# clock_generator.net
KiCad netlist of a schematic drawn in Altium Designer
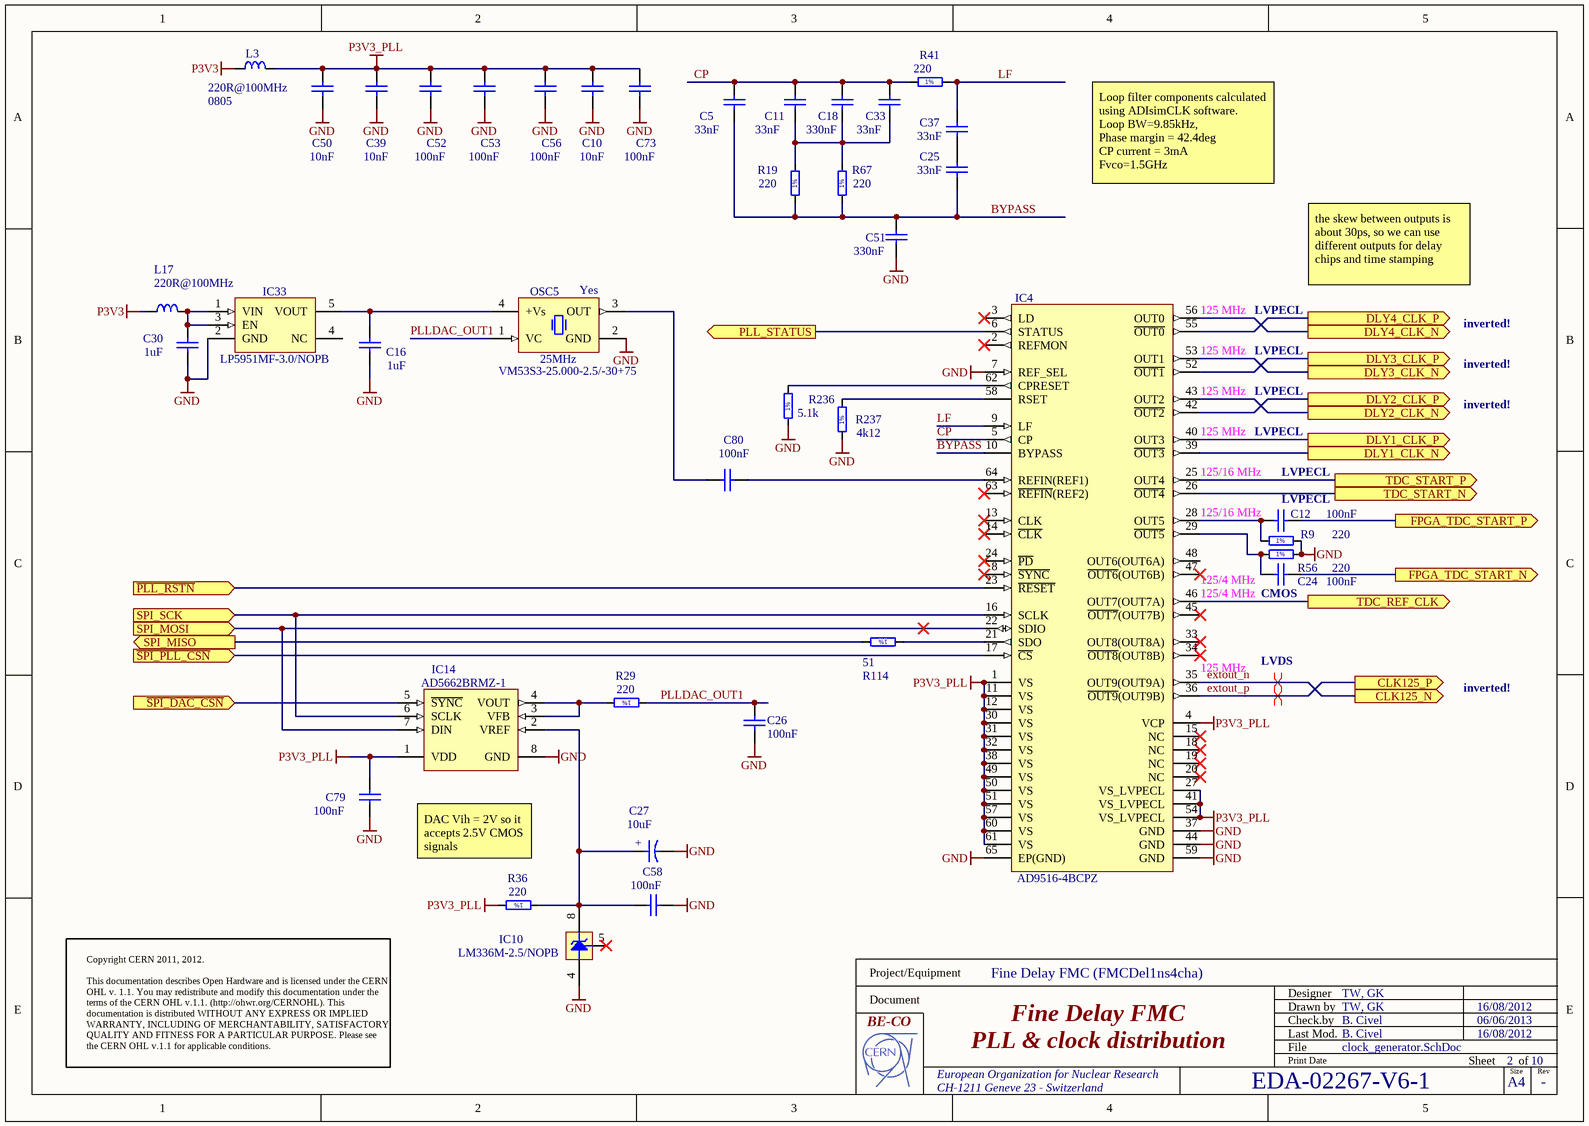
[diagram p0: clock_generator.SchDoc]

(export (version "E")
  (design (tool "Eeschema 10.0.6"))
  (components
    (comp (ref "C5")
      (value "33nF")
      (footprint "CAPC1608X87N")
      (description "Non-polarised capacitor")
      (fields
        (field (name "PART NUMBER") "CC0603_33NF_25V_10%_X7R")
        (field (name "VOLTAGE") "25V")
        (field (name "AUTHOR") "CERN DEM JLC")
      )
      (libsource (lib "Capacitors") (part "Capacitor - non polarized"))
    )
    (comp (ref "C10")
      (value "10nF")
      (footprint "CAPC1608X87N")
      (description "Non-polarised capacitor")
      (fields
        (field (name "PART NUMBER") "CC0603_10NF_50V_10%_X7R")
        (field (name "VOLTAGE") "50V")
        (field (name "AUTHOR") "CERN DEM JLC")
      )
      (libsource (lib "Capacitors") (part "Capacitor - non polarized"))
    )
    (comp (ref "C11")
      (value "33nF")
      (footprint "CAPC1608X87N")
      (description "Non-polarised capacitor")
      (fields
        (field (name "PART NUMBER") "CC0603_33NF_25V_10%_X7R")
        (field (name "VOLTAGE") "25V")
        (field (name "AUTHOR") "CERN DEM JLC")
      )
      (libsource (lib "Capacitors") (part "Capacitor - non polarized"))
    )
    (comp (ref "C12")
      (value "100nF")
      (footprint "CAPC1608X87N")
      (description "Non-polarised capacitor")
      (fields
        (field (name "PART NUMBER") "CC0603_100NF_50V_10%_X7R")
        (field (name "VOLTAGE") "50V")
        (field (name "AUTHOR") "CERN DEM JLC")
      )
      (libsource (lib "Capacitors") (part "Capacitor - non polarized"))
    )
    (comp (ref "C16")
      (value "1uF")
      (footprint "CAPC2012X140N")
      (description "Non-polarised capacitor")
      (fields
        (field (name "PART NUMBER") "CC0805_1UF_35V_20%_X7R")
        (field (name "VOLTAGE") "35V")
        (field (name "AUTHOR") "CERN DEM JLC")
      )
      (libsource (lib "Capacitors") (part "Capacitor - non polarized"))
    )
    (comp (ref "C18")
      (value "330nF")
      (footprint "CAPC1608X87N")
      (description "Non-polarised capacitor")
      (fields
        (field (name "PART NUMBER") "CC0603_330NF_16V_10%_X5R")
        (field (name "VOLTAGE") "16V")
        (field (name "AUTHOR") "CERN DEM JLC")
      )
      (libsource (lib "Capacitors") (part "Capacitor - non polarized"))
    )
    (comp (ref "C24")
      (value "100nF")
      (footprint "CAPC1608X87N")
      (description "Non-polarised capacitor")
      (fields
        (field (name "PART NUMBER") "CC0603_100NF_50V_10%_X7R")
        (field (name "VOLTAGE") "50V")
        (field (name "AUTHOR") "CERN DEM JLC")
      )
      (libsource (lib "Capacitors") (part "Capacitor - non polarized"))
    )
    (comp (ref "C25")
      (value "33nF")
      (footprint "CAPC1608X87N")
      (description "Non-polarised capacitor")
      (fields
        (field (name "PART NUMBER") "CC0603_33NF_25V_10%_X7R")
        (field (name "VOLTAGE") "25V")
        (field (name "AUTHOR") "CERN DEM JLC")
      )
      (libsource (lib "Capacitors") (part "Capacitor - non polarized"))
    )
    (comp (ref "C26")
      (value "100nF")
      (footprint "CAPC1608X87N")
      (description "Non-polarised capacitor")
      (fields
        (field (name "PART NUMBER") "CC0603_100NF_50V_10%_X7R")
        (field (name "VOLTAGE") "50V")
        (field (name "AUTHOR") "CERN DEM JLC")
      )
      (libsource (lib "Capacitors") (part "Capacitor - non polarized"))
    )
    (comp (ref "C27")
      (value "10uF")
      (footprint "CAPMP3528X210N")
      (description "Polarised capacitor")
      (fields
        (field (name "PART NUMBER") "CTE3528-21_10UF_16V_20%_SANYO_TQC")
        (field (name "VOLTAGE") "16V")
        (field (name "AUTHOR") "CERN DEM JLC")
      )
      (libsource (lib "Capacitors") (part "Capacitor - polarized"))
    )
    (comp (ref "C30")
      (value "1uF")
      (footprint "CAPC2012X140N")
      (description "Non-polarised capacitor")
      (fields
        (field (name "PART NUMBER") "CC0805_1UF_35V_20%_X7R")
        (field (name "VOLTAGE") "35V")
        (field (name "AUTHOR") "CERN DEM JLC")
      )
      (libsource (lib "Capacitors") (part "Capacitor - non polarized"))
    )
    (comp (ref "C33")
      (value "33nF")
      (footprint "CAPC1608X87N")
      (description "Non-polarised capacitor")
      (fields
        (field (name "PART NUMBER") "CC0603_33NF_25V_10%_X7R")
        (field (name "VOLTAGE") "25V")
        (field (name "AUTHOR") "CERN DEM JLC")
      )
      (libsource (lib "Capacitors") (part "Capacitor - non polarized"))
    )
    (comp (ref "C37")
      (value "33nF")
      (footprint "CAPC1608X87N")
      (description "Non-polarised capacitor")
      (fields
        (field (name "PART NUMBER") "CC0603_33NF_25V_10%_X7R")
        (field (name "VOLTAGE") "25V")
        (field (name "AUTHOR") "CERN DEM JLC")
      )
      (libsource (lib "Capacitors") (part "Capacitor - non polarized"))
    )
    (comp (ref "C39")
      (value "10nF")
      (footprint "CAPC1608X87N")
      (description "Non-polarised capacitor")
      (fields
        (field (name "PART NUMBER") "CC0603_10NF_50V_10%_X7R")
        (field (name "VOLTAGE") "50V")
        (field (name "AUTHOR") "CERN DEM JLC")
      )
      (libsource (lib "Capacitors") (part "Capacitor - non polarized"))
    )
    (comp (ref "C50")
      (value "10nF")
      (footprint "CAPC1608X87N")
      (description "Non-polarised capacitor")
      (fields
        (field (name "PART NUMBER") "CC0603_10NF_50V_10%_X7R")
        (field (name "VOLTAGE") "50V")
        (field (name "AUTHOR") "CERN DEM JLC")
      )
      (libsource (lib "Capacitors") (part "Capacitor - non polarized"))
    )
    (comp (ref "C51")
      (value "330nF")
      (footprint "CAPC1608X87N")
      (description "Non-polarised capacitor")
      (fields
        (field (name "PART NUMBER") "CC0603_330NF_16V_10%_X5R")
        (field (name "VOLTAGE") "16V")
        (field (name "AUTHOR") "CERN DEM JLC")
      )
      (libsource (lib "Capacitors") (part "Capacitor - non polarized"))
    )
    (comp (ref "C52")
      (value "100nF")
      (footprint "CAPC1608X87N")
      (description "Non-polarised capacitor")
      (fields
        (field (name "PART NUMBER") "CC0603_100NF_50V_10%_X7R")
        (field (name "VOLTAGE") "50V")
        (field (name "AUTHOR") "CERN DEM JLC")
      )
      (libsource (lib "Capacitors") (part "Capacitor - non polarized"))
    )
    (comp (ref "C53")
      (value "100nF")
      (footprint "CAPC1608X87N")
      (description "Non-polarised capacitor")
      (fields
        (field (name "PART NUMBER") "CC0603_100NF_50V_10%_X7R")
        (field (name "VOLTAGE") "50V")
        (field (name "AUTHOR") "CERN DEM JLC")
      )
      (libsource (lib "Capacitors") (part "Capacitor - non polarized"))
    )
    (comp (ref "C56")
      (value "100nF")
      (footprint "CAPC1608X87N")
      (description "Non-polarised capacitor")
      (fields
        (field (name "PART NUMBER") "CC0603_100NF_50V_10%_X7R")
        (field (name "VOLTAGE") "50V")
        (field (name "AUTHOR") "CERN DEM JLC")
      )
      (libsource (lib "Capacitors") (part "Capacitor - non polarized"))
    )
    (comp (ref "C58")
      (value "100nF")
      (footprint "CAPC1608X87N")
      (description "Non-polarised capacitor")
      (fields
        (field (name "PART NUMBER") "CC0603_100NF_50V_10%_X7R")
        (field (name "VOLTAGE") "50V")
        (field (name "AUTHOR") "CERN DEM JLC")
      )
      (libsource (lib "Capacitors") (part "Capacitor - non polarized"))
    )
    (comp (ref "C73")
      (value "100nF")
      (footprint "CAPC1608X87N")
      (description "Non-polarised capacitor")
      (fields
        (field (name "PART NUMBER") "CC0603_100NF_50V_10%_X7R")
        (field (name "VOLTAGE") "50V")
        (field (name "AUTHOR") "CERN DEM JLC")
      )
      (libsource (lib "Capacitors") (part "Capacitor - non polarized"))
    )
    (comp (ref "C79")
      (value "100nF")
      (footprint "CAPC1608X87N")
      (description "Non-polarised capacitor")
      (fields
        (field (name "MANUFACTURER1 PART NUMBER") "223858615649")
        (field (name "MANUFACTURER") "GENERIC")
        (field (name "AUTHOR") "CERN DEM JLC")
      )
      (libsource (lib "Capacitors") (part "Capacitor - non polarized"))
    )
    (comp (ref "C80")
      (value "100nF")
      (footprint "CAPC1608X87N")
      (description "Non-polarised capacitor")
      (fields
        (field (name "MANUFACTURER1 PART NUMBER") "223858615649")
        (field (name "MANUFACTURER") "GENERIC")
        (field (name "AUTHOR") "CERN DEM JLC")
      )
      (libsource (lib "Capacitors") (part "Capacitor - non polarized"))
    )
    (comp (ref "IC4")
      (value "AD9516-4BCPZ")
      (footprint "QFN50P900X900X100-65N-S635")
      (description "14-Output Clock Generator with Integrated 1.6 GHz VCO")
      (fields (field (name "MANUFACTURER") "ANALOG DEVICES") (field (name "AUTHOR") "CERN DEM JLC"))
      (libsource (lib "ICs And Semiconductors") (part "AD9516-4"))
    )
    (comp (ref "IC10")
      (value "LM336M-2.5/NOPB")
      (footprint "SOIC127P600X175-8N")
      (description "Reference Diode")
      (fields (field (name "MANUFACTURER") "TEXAS INSTRUMENTS") (field (name "AUTHOR") "CERN DEM JLC"))
      (libsource (lib "ICs And Semiconductors") (part "LM336M-2.5"))
    )
    (comp (ref "IC14")
      (value "AD5662BRMZ-1")
      (footprint "SOP65P490X110-8N")
      (description "2.7V to 5.5V, 250uA, Rail-to-Rail Output 16-Bit nanoDAC")
      (fields (field (name "MANUFACTURER") "ANALOG DEVICES") (field (name "AUTHOR") "CERN DEM JLC"))
      (libsource (lib "ICs And Semiconductors") (part "AD5662"))
    )
    (comp (ref "IC33")
      (value "LP5951MF-3.0/NOPB")
      (footprint "SOT95P284X122-5N")
      (description "150mA Micropower Low-Dropout CMOS Voltage Regulator")
      (fields (field (name "MANUFACTURER") "TEXAS INSTRUMENTS") (field (name "AUTHOR") "CERN DEM JLC"))
      (libsource (lib "ICs And Semiconductors") (part "LP5951"))
    )
    (comp (ref "L3")
      (value "220R@100MHz")
      (footprint "INDC2012X105N")
      (description "Inductor")
      (fields
        (field (name "PART NUMBER") "IND0805_MURATA_BLM21PG221SN1D")
        (field (name "POWER") "2A")
        (field (name "CASE") "0805")
        (field (name "AUTHOR") "CERN DEM JLC")
      )
      (libsource (lib "Inductors & Transformers") (part "Inductor"))
    )
    (comp (ref "L17")
      (value "220R@100MHz")
      (footprint "INDC2012X105N")
      (description "Inductor")
      (fields
        (field (name "PART NUMBER") "IND0805_MURATA_BLM21PG221SN1D")
        (field (name "POWER") "2A")
        (field (name "AUTHOR") "CERN DEM JLC")
      )
      (libsource (lib "Inductors & Transformers") (part "Inductor"))
    )
    (comp (ref "OSC5")
      (value "25MHz")
      (footprint "OSCCC320X500X160-4N")
      (description "Oscillator 4 pins 1=VC 2=GND 3=OUT 4=+Vs")
      (fields
        (field (name "PART NUMBER") "OSC_25MHZ_MERCURY_VM53S3-25.000-2.5/-30+75")
        (field (name "MANUFACTURER") "MERCURY ELECTRONICS")
        (field (name "MANUFACTURER PART NUMBER") "VM53S3-25.000-2.5/-30+75")
        (field (name "MOUNTED") "Yes")
        (field (name "AUTHOR") "CERN DEM JLC")
      )
      (libsource (lib "ICs And Semiconductors") (part "Oscillator 1VC 2GND 3OUT 4+Vs"))
    )
    (comp (ref "R9")
      (value "220")
      (footprint "RESC1608X55N")
      (description "Resistor - 1%")
      (fields
        (field (name "PART NUMBER") "R0603_220R_1%_0.1W_100PPM")
        (field (name "POWER") "0.1W")
        (field (name "AUTHOR") "CERN DEM JLC")
      )
      (libsource (lib "Resistors") (part "Resistor - 1%"))
    )
    (comp (ref "R19")
      (value "220")
      (footprint "RESC1608X55N")
      (description "Resistor - 1%")
      (fields
        (field (name "PART NUMBER") "R0603_220R_1%_0.1W_100PPM")
        (field (name "POWER") "0.1W")
        (field (name "AUTHOR") "CERN DEM JLC")
      )
      (libsource (lib "Resistors") (part "Resistor - 1%"))
    )
    (comp (ref "R29")
      (value "220")
      (footprint "RESC1608X55N")
      (description "Resistor - 1%")
      (fields
        (field (name "PART NUMBER") "R0603_220R_1%_0.1W_100PPM")
        (field (name "POWER") "0.1W")
        (field (name "AUTHOR") "CERN DEM JLC")
      )
      (libsource (lib "Resistors") (part "Resistor - 1%"))
    )
    (comp (ref "R36")
      (value "220")
      (footprint "RESC1608X55N")
      (description "Resistor - 1%")
      (fields
        (field (name "PART NUMBER") "R0603_220R_1%_0.1W_100PPM")
        (field (name "POWER") "0.1W")
        (field (name "AUTHOR") "CERN DEM JLC")
      )
      (libsource (lib "Resistors") (part "Resistor - 1%"))
    )
    (comp (ref "R41")
      (value "220")
      (footprint "RESC1608X55N")
      (description "Resistor - 1%")
      (fields
        (field (name "PART NUMBER") "R0603_220R_1%_0.1W_100PPM")
        (field (name "POWER") "0.1W")
        (field (name "AUTHOR") "CERN DEM JLC")
      )
      (libsource (lib "Resistors") (part "Resistor - 1%"))
    )
    (comp (ref "R56")
      (value "220")
      (footprint "RESC1608X55N")
      (description "Resistor - 1%")
      (fields
        (field (name "PART NUMBER") "R0603_220R_1%_0.1W_100PPM")
        (field (name "POWER") "0.1W")
        (field (name "AUTHOR") "CERN DEM JLC")
      )
      (libsource (lib "Resistors") (part "Resistor - 1%"))
    )
    (comp (ref "R67")
      (value "220")
      (footprint "RESC1608X55N")
      (description "Resistor - 1%")
      (fields
        (field (name "PART NUMBER") "R0603_220R_1%_0.1W_100PPM")
        (field (name "POWER") "0.1W")
        (field (name "AUTHOR") "CERN DEM JLC")
      )
      (libsource (lib "Resistors") (part "Resistor - 1%"))
    )
    (comp (ref "R114")
      (value "51")
      (footprint "RESC1608X55N")
      (description "Resistor - 1%")
      (fields
        (field (name "PART NUMBER") "R0603_51R_1%_0.1W_100PPM")
        (field (name "POWER") "0.1W")
        (field (name "AUTHOR") "CERN DEM JLC")
      )
      (libsource (lib "Resistors") (part "Resistor - 1%"))
    )
    (comp (ref "R236")
      (value "5.1k")
      (footprint "RESC1608X55N")
      (description "Resistor - 1%")
      (fields
        (field (name "PART NUMBER") "R0603_5K1_1%_0.1W_100PPM")
        (field (name "POWER") "0.1W")
        (field (name "AUTHOR") "CERN DEM JLC")
      )
      (libsource (lib "Resistors") (part "Resistor - 1%"))
    )
    (comp (ref "R237")
      (value "4k12")
      (footprint "RESC1608X55N")
      (description "Resistor - 1%")
      (fields
        (field (name "PART NUMBER") "R0603_4K12_1%_0.1W_100PPM")
        (field (name "POWER") "0.1W")
        (field (name "AUTHOR") "CERN DEM JLC")
      )
      (libsource (lib "Resistors") (part "Resistor - 1%"))
    )
  )
  (nets
    (net (code "1") (name "/BYPASS") (class "Default")
      (node (ref "C25") (pin "1") (pinfunction "1_1") (pintype "passive"))
      (node (ref "C5") (pin "1") (pinfunction "1_1") (pintype "passive"))
      (node (ref "C51") (pin "2") (pinfunction "2_2") (pintype "passive"))
      (node (ref "IC4") (pin "10") (pinfunction "BYPASS_10") (pintype "passive"))
      (node (ref "R19") (pin "1") (pinfunction "1_1") (pintype "passive"))
      (node (ref "R67") (pin "1") (pinfunction "1_1") (pintype "passive"))
    )
    (net (code "2") (name "/CP") (class "Default")
      (node (ref "C11") (pin "2") (pinfunction "2_2") (pintype "passive"))
      (node (ref "C18") (pin "2") (pinfunction "2_2") (pintype "passive"))
      (node (ref "C33") (pin "2") (pinfunction "2_2") (pintype "passive"))
      (node (ref "C5") (pin "2") (pinfunction "2_2") (pintype "passive"))
      (node (ref "IC4") (pin "5") (pinfunction "CP_5") (pintype "output"))
      (node (ref "R41") (pin "1") (pinfunction "1_1") (pintype "passive"))
    )
    (net (code "3") (name "/DLY1_CLK_N") (class "Default")
      (node (ref "IC4") (pin "39") (pinfunction "OUT3_39") (pintype "output"))
    )
    (net (code "4") (name "/DLY1_CLK_P") (class "Default")
      (node (ref "IC4") (pin "40") (pinfunction "OUT3_40") (pintype "output"))
    )
    (net (code "5") (name "/DLY2_CLK_N") (class "Default")
      (node (ref "IC4") (pin "43") (pinfunction "OUT2_43") (pintype "output"))
    )
    (net (code "6") (name "/DLY2_CLK_P") (class "Default")
      (node (ref "IC4") (pin "42") (pinfunction "OUT2_42") (pintype "output"))
    )
    (net (code "7") (name "/DLY3_CLK_N") (class "Default")
      (node (ref "IC4") (pin "53") (pinfunction "OUT1_53") (pintype "output"))
    )
    (net (code "8") (name "/DLY3_CLK_P") (class "Default")
      (node (ref "IC4") (pin "52") (pinfunction "OUT1_52") (pintype "output"))
    )
    (net (code "9") (name "/DLY4_CLK_N") (class "Default")
      (node (ref "IC4") (pin "56") (pinfunction "OUT0_56") (pintype "output"))
    )
    (net (code "10") (name "/DLY4_CLK_P") (class "Default")
      (node (ref "IC4") (pin "55") (pinfunction "OUT0_55") (pintype "output"))
    )
    (net (code "11") (name "/FPGA_TDC_START_N") (class "Default")
      (node (ref "C24") (pin "1") (pinfunction "1_1") (pintype "passive"))
    )
    (net (code "12") (name "/FPGA_TDC_START_P") (class "Default")
      (node (ref "C12") (pin "1") (pinfunction "1_1") (pintype "passive"))
    )
    (net (code "13") (name "/LF") (class "Default")
      (node (ref "C37") (pin "2") (pinfunction "2_2") (pintype "passive"))
      (node (ref "IC4") (pin "9") (pinfunction "LF_9") (pintype "input"))
      (node (ref "R41") (pin "2") (pinfunction "2_2") (pintype "passive"))
    )
    (net (code "14") (name "/PLLDAC_OUT1") (class "Default")
      (node (ref "C26") (pin "1") (pinfunction "1_1") (pintype "passive"))
      (node (ref "OSC5") (pin "1") (pinfunction "VC_1") (pintype "input"))
      (node (ref "R29") (pin "1") (pinfunction "1_1") (pintype "passive"))
    )
    (net (code "15") (name "/PLL_RSTN") (class "Default")
      (node (ref "IC4") (pin "23") (pinfunction "RESET_23") (pintype "input"))
    )
    (net (code "16") (name "/PLL_STATUS") (class "Default")
      (node (ref "IC4") (pin "6") (pinfunction "STATUS_6") (pintype "output"))
    )
    (net (code "17") (name "/SPI_DAC_CSN") (class "Default")
      (node (ref "IC14") (pin "5") (pinfunction "~{SYNC}_5") (pintype "input"))
    )
    (net (code "18") (name "/SPI_MISO") (class "Default")
      (node (ref "R114") (pin "2") (pinfunction "2_2") (pintype "passive"))
    )
    (net (code "19") (name "/SPI_MOSI") (class "Default")
      (node (ref "IC14") (pin "7") (pinfunction "DIN_7") (pintype "input"))
      (node (ref "IC4") (pin "22") (pinfunction "SDIO_22") (pintype "bidirectional"))
    )
    (net (code "20") (name "/SPI_PLL_CSN") (class "Default")
      (node (ref "IC4") (pin "17") (pinfunction "CS_17") (pintype "input"))
    )
    (net (code "21") (name "/SPI_SCK") (class "Default")
      (node (ref "IC14") (pin "6") (pinfunction "SCLK_6") (pintype "input"))
      (node (ref "IC4") (pin "16") (pinfunction "SCLK_16") (pintype "input"))
    )
    (net (code "22") (name "/TDC_REF_CLK") (class "Default")
      (node (ref "IC4") (pin "46") (pinfunction "OUT7(OUT7A)_46") (pintype "output"))
    )
    (net (code "23") (name "/TDC_START_N") (class "Default")
      (node (ref "IC4") (pin "26") (pinfunction "OUT4_26") (pintype "output"))
    )
    (net (code "24") (name "/TDC_START_P") (class "Default")
      (node (ref "IC4") (pin "25") (pinfunction "OUT4_25") (pintype "output"))
    )
    (net (code "25") (name "/extout_n") (class "Default")
      (node (ref "IC4") (pin "35") (pinfunction "OUT9(OUT9A)_35") (pintype "output"))
    )
    (net (code "26") (name "/extout_p") (class "Default")
      (node (ref "IC4") (pin "36") (pinfunction "~{OUT9}(OUT9B)_36") (pintype "output"))
    )
    (net (code "27") (name "GND") (class "Default")
      (node (ref "C10") (pin "2") (pinfunction "2_2") (pintype "passive"))
      (node (ref "C16") (pin "2") (pinfunction "2_2") (pintype "passive"))
      (node (ref "C26") (pin "2") (pinfunction "2_2") (pintype "passive"))
      (node (ref "C27") (pin "2") (pinfunction "2_2") (pintype "passive"))
      (node (ref "C30") (pin "2") (pinfunction "2_2") (pintype "passive"))
      (node (ref "C39") (pin "2") (pinfunction "2_2") (pintype "passive"))
      (node (ref "C50") (pin "2") (pinfunction "2_2") (pintype "passive"))
      (node (ref "C51") (pin "1") (pinfunction "1_1") (pintype "passive"))
      (node (ref "C52") (pin "1") (pinfunction "1_1") (pintype "passive"))
      (node (ref "C53") (pin "1") (pinfunction "1_1") (pintype "passive"))
      (node (ref "C56") (pin "1") (pinfunction "1_1") (pintype "passive"))
      (node (ref "C58") (pin "1") (pinfunction "1_1") (pintype "passive"))
      (node (ref "C73") (pin "1") (pinfunction "1_1") (pintype "passive"))
      (node (ref "C79") (pin "1") (pinfunction "1_1") (pintype "passive"))
      (node (ref "IC10") (pin "4") (pinfunction "A_4") (pintype "passive"))
      (node (ref "IC14") (pin "8") (pinfunction "GND_8") (pintype "power_in"))
      (node (ref "IC33") (pin "2") (pinfunction "GND_2") (pintype "power_in"))
      (node (ref "IC4") (pin "37") (pinfunction "GND_37") (pintype "power_in"))
      (node (ref "IC4") (pin "44") (pinfunction "GND_44") (pintype "power_in"))
      (node (ref "IC4") (pin "59") (pinfunction "GND_59") (pintype "power_in"))
      (node (ref "IC4") (pin "65") (pinfunction "EP(GND)_65") (pintype "power_in"))
      (node (ref "IC4") (pin "7") (pinfunction "REF_SEL_7") (pintype "input"))
      (node (ref "OSC5") (pin "2") (pinfunction "GND_2") (pintype "power_in"))
      (node (ref "R236") (pin "1") (pinfunction "1_1") (pintype "passive"))
      (node (ref "R237") (pin "1") (pinfunction "1_1") (pintype "passive"))
      (node (ref "R56") (pin "2") (pinfunction "2_2") (pintype "passive"))
      (node (ref "R9") (pin "2") (pinfunction "2_2") (pintype "passive"))
    )
    (net (code "28") (name "Net-(C11-Pad1)") (class "Default")
      (node (ref "C11") (pin "1") (pinfunction "1_1") (pintype "passive"))
      (node (ref "C18") (pin "1") (pinfunction "1_1") (pintype "passive"))
      (node (ref "C33") (pin "1") (pinfunction "1_1") (pintype "passive"))
      (node (ref "R19") (pin "2") (pinfunction "2_2") (pintype "passive"))
      (node (ref "R67") (pin "2") (pinfunction "2_2") (pintype "passive"))
    )
    (net (code "29") (name "Net-(C12-Pad2)") (class "Default")
      (node (ref "C12") (pin "2") (pinfunction "2_2") (pintype "passive"))
      (node (ref "IC4") (pin "28") (pinfunction "OUT5_28") (pintype "output"))
      (node (ref "R9") (pin "1") (pinfunction "1_1") (pintype "passive"))
    )
    (net (code "30") (name "Net-(C24-Pad2)") (class "Default")
      (node (ref "C24") (pin "2") (pinfunction "2_2") (pintype "passive"))
      (node (ref "IC4") (pin "29") (pinfunction "OUT5_29") (pintype "output"))
      (node (ref "R56") (pin "1") (pinfunction "1_1") (pintype "passive"))
    )
    (net (code "31") (name "Net-(C25-Pad2)") (class "Default")
      (node (ref "C25") (pin "2") (pinfunction "2_2") (pintype "passive"))
      (node (ref "C37") (pin "1") (pinfunction "1_1") (pintype "passive"))
    )
    (net (code "32") (name "Net-(IC4-CPRESET)") (class "Default")
      (node (ref "IC4") (pin "62") (pinfunction "CPRESET_62") (pintype "output"))
      (node (ref "R236") (pin "2") (pinfunction "2_2") (pintype "passive"))
    )
    (net (code "33") (name "Net-(IC4-REFIN(REF1))") (class "Default")
      (node (ref "C80") (pin "1") (pinfunction "1_1") (pintype "passive"))
      (node (ref "IC4") (pin "64") (pinfunction "REFIN(REF1)_64") (pintype "input"))
    )
    (net (code "34") (name "Net-(IC4-RSET)") (class "Default")
      (node (ref "IC4") (pin "58") (pinfunction "RSET_58") (pintype "passive"))
      (node (ref "R237") (pin "2") (pinfunction "2_2") (pintype "passive"))
    )
    (net (code "35") (name "Net-(IC4-SDO)") (class "Default")
      (node (ref "IC4") (pin "21") (pinfunction "SDO_21") (pintype "output"))
      (node (ref "R114") (pin "1") (pinfunction "1_1") (pintype "passive"))
    )
    (net (code "36") (name "Net-(IC10-C)") (class "Default")
      (node (ref "C27") (pin "1") (pinfunction "1_1") (pintype "passive"))
      (node (ref "C58") (pin "2") (pinfunction "2_2") (pintype "passive"))
      (node (ref "IC10") (pin "8") (pinfunction "C_8") (pintype "passive"))
      (node (ref "IC14") (pin "2") (pinfunction "VREF_2") (pintype "input"))
      (node (ref "R36") (pin "1") (pinfunction "1_1") (pintype "passive"))
    )
    (net (code "37") (name "Net-(IC14-VFB)") (class "Default")
      (node (ref "IC14") (pin "3") (pinfunction "VFB_3") (pintype "input"))
      (node (ref "IC14") (pin "4") (pinfunction "VOUT_4") (pintype "output"))
      (node (ref "R29") (pin "2") (pinfunction "2_2") (pintype "passive"))
    )
    (net (code "38") (name "Net-(IC33-EN)") (class "Default")
      (node (ref "C30") (pin "1") (pinfunction "1_1") (pintype "passive"))
      (node (ref "IC33") (pin "1") (pinfunction "VIN_1") (pintype "input"))
      (node (ref "IC33") (pin "3") (pinfunction "EN_3") (pintype "input"))
      (node (ref "L17") (pin "2") (pinfunction "2_2") (pintype "passive"))
    )
    (net (code "39") (name "Net-(IC33-VOUT)") (class "Default")
      (node (ref "C16") (pin "1") (pinfunction "1_1") (pintype "passive"))
      (node (ref "IC33") (pin "5") (pinfunction "VOUT_5") (pintype "power_in"))
      (node (ref "OSC5") (pin "4") (pinfunction "+Vs_4") (pintype "power_in"))
    )
    (net (code "40") (name "Net-(OSC5-OUT)") (class "Default")
      (node (ref "C80") (pin "2") (pinfunction "2_2") (pintype "passive"))
      (node (ref "OSC5") (pin "3") (pinfunction "OUT_3") (pintype "output"))
    )
    (net (code "41") (name "P3V3") (class "Default")
      (node (ref "L17") (pin "1") (pinfunction "1_1") (pintype "passive"))
      (node (ref "L3") (pin "1") (pinfunction "1_1") (pintype "passive"))
    )
    (net (code "42") (name "P3V3_PLL") (class "Default")
      (node (ref "C10") (pin "1") (pinfunction "1_1") (pintype "passive"))
      (node (ref "C39") (pin "1") (pinfunction "1_1") (pintype "passive"))
      (node (ref "C50") (pin "1") (pinfunction "1_1") (pintype "passive"))
      (node (ref "C52") (pin "2") (pinfunction "2_2") (pintype "passive"))
      (node (ref "C53") (pin "2") (pinfunction "2_2") (pintype "passive"))
      (node (ref "C56") (pin "2") (pinfunction "2_2") (pintype "passive"))
      (node (ref "C73") (pin "2") (pinfunction "2_2") (pintype "passive"))
      (node (ref "C79") (pin "2") (pinfunction "2_2") (pintype "passive"))
      (node (ref "IC14") (pin "1") (pinfunction "VDD_1") (pintype "power_in"))
      (node (ref "IC4") (pin "1") (pinfunction "VS_1") (pintype "power_in"))
      (node (ref "IC4") (pin "11") (pinfunction "VS_11") (pintype "power_in"))
      (node (ref "IC4") (pin "12") (pinfunction "VS_12") (pintype "power_in"))
      (node (ref "IC4") (pin "27") (pinfunction "VS_LVPECL_27") (pintype "power_in"))
      (node (ref "IC4") (pin "30") (pinfunction "VS_30") (pintype "power_in"))
      (node (ref "IC4") (pin "31") (pinfunction "VS_31") (pintype "power_in"))
      (node (ref "IC4") (pin "32") (pinfunction "VS_32") (pintype "power_in"))
      (node (ref "IC4") (pin "38") (pinfunction "VS_38") (pintype "power_in"))
      (node (ref "IC4") (pin "4") (pinfunction "VCP_4") (pintype "power_in"))
      (node (ref "IC4") (pin "41") (pinfunction "VS_LVPECL_41") (pintype "power_in"))
      (node (ref "IC4") (pin "49") (pinfunction "VS_49") (pintype "power_in"))
      (node (ref "IC4") (pin "50") (pinfunction "VS_50") (pintype "power_in"))
      (node (ref "IC4") (pin "51") (pinfunction "VS_51") (pintype "power_in"))
      (node (ref "IC4") (pin "54") (pinfunction "VS_LVPECL_54") (pintype "power_in"))
      (node (ref "IC4") (pin "57") (pinfunction "VS_57") (pintype "power_in"))
      (node (ref "IC4") (pin "60") (pinfunction "VS_60") (pintype "power_in"))
      (node (ref "IC4") (pin "61") (pinfunction "VS_61") (pintype "power_in"))
      (node (ref "L3") (pin "2") (pinfunction "2_2") (pintype "passive"))
      (node (ref "R36") (pin "2") (pinfunction "2_2") (pintype "passive"))
    )
    (net (code "43") (name "unconnected-(IC4-CLK-Pad13)") (class "Default")
      (node (ref "IC4") (pin "13") (pinfunction "CLK_13") (pintype "input+no_connect"))
    )
    (net (code "44") (name "unconnected-(IC4-CLK-Pad14)") (class "Default")
      (node (ref "IC4") (pin "14") (pinfunction "CLK_14") (pintype "input+no_connect"))
    )
    (net (code "45") (name "unconnected-(IC4-LD-Pad3)") (class "Default")
      (node (ref "IC4") (pin "3") (pinfunction "LD_3") (pintype "output+no_connect"))
    )
    (net (code "46") (name "unconnected-(IC4-NC-Pad15)") (class "Default")
      (node (ref "IC4") (pin "15") (pinfunction "NC_15") (pintype "passive+no_connect"))
    )
    (net (code "47") (name "unconnected-(IC4-NC-Pad18)") (class "Default")
      (node (ref "IC4") (pin "18") (pinfunction "NC_18") (pintype "passive+no_connect"))
    )
    (net (code "48") (name "unconnected-(IC4-NC-Pad19)") (class "Default")
      (node (ref "IC4") (pin "19") (pinfunction "NC_19") (pintype "passive+no_connect"))
    )
    (net (code "49") (name "unconnected-(IC4-NC-Pad20)") (class "Default")
      (node (ref "IC4") (pin "20") (pinfunction "NC_20") (pintype "passive+no_connect"))
    )
    (net (code "50") (name "unconnected-(IC4-OUT6(OUT6A)-Pad48)") (class "Default")
      (node (ref "IC4") (pin "48") (pinfunction "OUT6(OUT6A)_48") (pintype "output"))
    )
    (net (code "51") (name "unconnected-(IC4-OUT8(OUT8A)-Pad33)") (class "Default")
      (node (ref "IC4") (pin "33") (pinfunction "OUT8(OUT8A)_33") (pintype "output+no_connect"))
    )
    (net (code "52") (name "unconnected-(IC4-PD-Pad24)") (class "Default")
      (node (ref "IC4") (pin "24") (pinfunction "PD_24") (pintype "input+no_connect"))
    )
    (net (code "53") (name "unconnected-(IC4-REFMON-Pad2)") (class "Default")
      (node (ref "IC4") (pin "2") (pinfunction "REFMON_2") (pintype "output+no_connect"))
    )
    (net (code "54") (name "unconnected-(IC4-SYNC-Pad8)") (class "Default")
      (node (ref "IC4") (pin "8") (pinfunction "SYNC_8") (pintype "input+no_connect"))
    )
    (net (code "55") (name "unconnected-(IC4-~{OUT6}(OUT6B)-Pad47)") (class "Default")
      (node (ref "IC4") (pin "47") (pinfunction "~{OUT6}(OUT6B)_47") (pintype "output+no_connect"))
    )
    (net (code "56") (name "unconnected-(IC4-~{OUT7}(OUT7B)-Pad45)") (class "Default")
      (node (ref "IC4") (pin "45") (pinfunction "~{OUT7}(OUT7B)_45") (pintype "output+no_connect"))
    )
    (net (code "57") (name "unconnected-(IC4-~{OUT8}(OUT8B)-Pad34)") (class "Default")
      (node (ref "IC4") (pin "34") (pinfunction "~{OUT8}(OUT8B)_34") (pintype "output+no_connect"))
    )
    (net (code "58") (name "unconnected-(IC4-~{REFIN}(REF2)-Pad63)") (class "Default")
      (node (ref "IC4") (pin "63") (pinfunction "~{REFIN}(REF2)_63") (pintype "input+no_connect"))
    )
    (net (code "59") (name "unconnected-(IC10-Adj-Pad5)") (class "Default")
      (node (ref "IC10") (pin "5") (pinfunction "Adj_5") (pintype "passive+no_connect"))
    )
    (net (code "60") (name "unconnected-(IC33-NC-Pad4)") (class "Default")
      (node (ref "IC33") (pin "4") (pinfunction "NC_4") (pintype "passive"))
    )
  )
)
